# LokomotivRevB.net
KiCad netlist of a schematic drawn in EAGLE
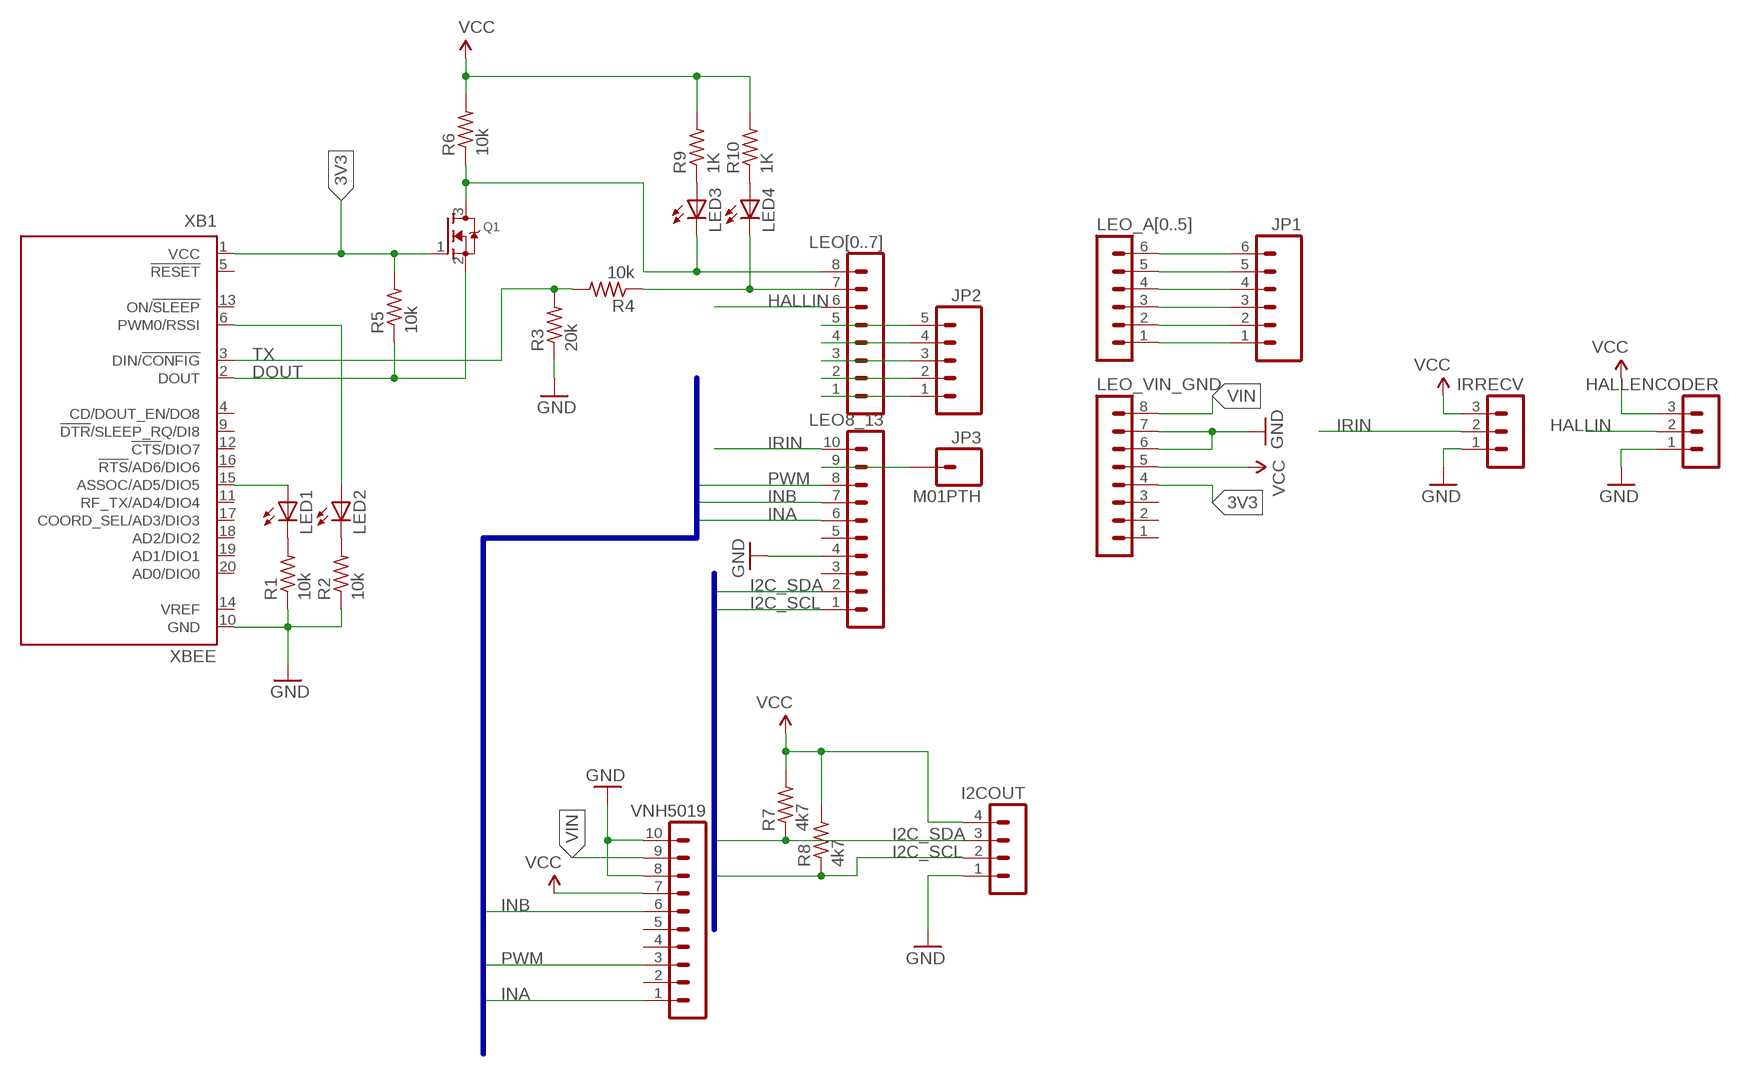
[diagram p0: schematic, sheet 1]

(export (version "E")
  (design (tool "Eeschema 10.0.6"))
  (components
    (comp (ref "HALLENCODER")
      (value "MA03-1")
      (footprint "eagle-import:MA03-1")
      (libsource (lib "eagle-import") (part "MA03-1"))
    )
    (comp (ref "I2COUT")
      (value "MA04-1")
      (footprint "eagle-import:MA04-1")
      (libsource (lib "eagle-import") (part "MA04-1"))
    )
    (comp (ref "IRRECV")
      (value "MA03-1")
      (footprint "eagle-import:MA03-1")
      (libsource (lib "eagle-import") (part "MA03-1"))
    )
    (comp (ref "JP1")
      (value "M06SIP")
      (footprint "eagle-import:1X06")
      (libsource (lib "eagle-import") (part "M06SIP"))
    )
    (comp (ref "JP2")
      (value "M05PTH")
      (footprint "eagle-import:1X05")
      (libsource (lib "eagle-import") (part "M05PTH"))
    )
    (comp (ref "JP3")
      (value "M01PTH")
      (footprint "eagle-import:1X01")
      (libsource (lib "eagle-import") (part "M01PTH"))
    )
    (comp (ref "LED1")
      (value "LEDCHIP-LED0805")
      (footprint "eagle-import:CHIP-LED0805")
      (libsource (lib "eagle-import") (part "LEDCHIP-LED0805"))
    )
    (comp (ref "LED2")
      (value "LEDCHIP-LED0805")
      (footprint "eagle-import:CHIP-LED0805")
      (libsource (lib "eagle-import") (part "LEDCHIP-LED0805"))
    )
    (comp (ref "LED3")
      (value "LEDCHIP-LED0805")
      (footprint "eagle-import:CHIP-LED0805")
      (libsource (lib "eagle-import") (part "LEDCHIP-LED0805"))
    )
    (comp (ref "LED4")
      (value "LEDCHIP-LED0805")
      (footprint "eagle-import:CHIP-LED0805")
      (libsource (lib "eagle-import") (part "LEDCHIP-LED0805"))
    )
    (comp (ref "LEO8_13")
      (value "MA10-1")
      (footprint "eagle-import:MA10-1")
      (libsource (lib "eagle-import") (part "MA10-1"))
    )
    (comp (ref "LEO[0..7]")
      (value "MA08-1")
      (footprint "eagle-import:MA08-1")
      (libsource (lib "eagle-import") (part "MA08-1"))
    )
    (comp (ref "LEO_A[0..5]")
      (value "MA06-1")
      (footprint "eagle-import:MA06-1")
      (libsource (lib "eagle-import") (part "MA06-1"))
    )
    (comp (ref "LEO_VIN_GND")
      (value "MA08-1")
      (footprint "eagle-import:MA08-1")
      (libsource (lib "eagle-import") (part "MA08-1"))
    )
    (comp (ref "Q1")
      (value "MOSFET-NREFLOW")
      (footprint "eagle-import:SOT23")
      (libsource (lib "eagle-import") (part "MOSFET-NREFLOW"))
    )
    (comp (ref "R1")
      (value "10k")
      (footprint "eagle-import:R0805")
      (libsource (lib "eagle-import") (part "R-US_R0805"))
    )
    (comp (ref "R2")
      (value "10k")
      (footprint "eagle-import:R0805")
      (libsource (lib "eagle-import") (part "R-US_R0805"))
    )
    (comp (ref "R3")
      (value "20k")
      (footprint "eagle-import:R0805")
      (libsource (lib "eagle-import") (part "R-US_R0805"))
    )
    (comp (ref "R4")
      (value "10k")
      (footprint "eagle-import:R0805")
      (libsource (lib "eagle-import") (part "R-US_R0805"))
    )
    (comp (ref "R5")
      (value "10k")
      (footprint "eagle-import:R0805")
      (libsource (lib "eagle-import") (part "R-US_R0805"))
    )
    (comp (ref "R6")
      (value "10k")
      (footprint "eagle-import:R0805")
      (libsource (lib "eagle-import") (part "R-US_R0805"))
    )
    (comp (ref "R7")
      (value "4k7")
      (footprint "eagle-import:R0805")
      (libsource (lib "eagle-import") (part "R-US_R0805"))
    )
    (comp (ref "R8")
      (value "4k7")
      (footprint "eagle-import:R0805")
      (libsource (lib "eagle-import") (part "R-US_R0805"))
    )
    (comp (ref "R9")
      (value "1K")
      (footprint "eagle-import:R0805")
      (libsource (lib "eagle-import") (part "R-US_R0805"))
    )
    (comp (ref "R10")
      (value "1K")
      (footprint "eagle-import:R0805")
      (libsource (lib "eagle-import") (part "R-US_R0805"))
    )
    (comp (ref "VNH5019")
      (value "MA10-1")
      (footprint "eagle-import:MA10-1")
      (libsource (lib "eagle-import") (part "MA10-1"))
    )
    (comp (ref "XB1")
      (value "XBEE")
      (footprint "eagle-import:XBEE")
      (fields (field (name "MPN") "XBP24-Z7UIT-004"))
      (libsource (lib "eagle-import") (part "XBEE"))
    )
  )
  (nets
    (net (code "1") (name "/DOUT") (class "Default")
      (node (ref "Q1") (pin "2") (pinfunction "S_2") (pintype "bidirectional"))
      (node (ref "R5") (pin "1") (pinfunction "1_1") (pintype "passive"))
      (node (ref "XB1") (pin "2") (pinfunction "DOUT_2") (pintype "output"))
    )
    (net (code "2") (name "/HALLIN") (class "Default")
      (node (ref "HALLENCODER") (pin "2") (pinfunction "2_2") (pintype "passive"))
      (node (ref "LEO[0..7]") (pin "6") (pinfunction "6_6") (pintype "passive"))
    )
    (net (code "3") (name "/I2C_SCL") (class "Default")
      (node (ref "I2COUT") (pin "2") (pinfunction "2_2") (pintype "passive"))
      (node (ref "LEO8_13") (pin "1") (pinfunction "1_1") (pintype "passive"))
      (node (ref "R8") (pin "1") (pinfunction "1_1") (pintype "passive"))
    )
    (net (code "4") (name "/I2C_SDA") (class "Default")
      (node (ref "I2COUT") (pin "3") (pinfunction "3_3") (pintype "passive"))
      (node (ref "LEO8_13") (pin "2") (pinfunction "2_2") (pintype "passive"))
      (node (ref "R7") (pin "1") (pinfunction "1_1") (pintype "passive"))
    )
    (net (code "5") (name "/INA") (class "Default")
      (node (ref "LEO8_13") (pin "6") (pinfunction "6_6") (pintype "passive"))
      (node (ref "VNH5019") (pin "1") (pinfunction "1_1") (pintype "passive"))
    )
    (net (code "6") (name "/INB") (class "Default")
      (node (ref "LEO8_13") (pin "7") (pinfunction "7_7") (pintype "passive"))
      (node (ref "VNH5019") (pin "6") (pinfunction "6_6") (pintype "passive"))
    )
    (net (code "7") (name "/IRIN") (class "Default")
      (node (ref "IRRECV") (pin "2") (pinfunction "2_2") (pintype "passive"))
      (node (ref "LEO8_13") (pin "10") (pinfunction "10_10") (pintype "passive"))
    )
    (net (code "8") (name "/PWM") (class "Default")
      (node (ref "LEO8_13") (pin "8") (pinfunction "8_8") (pintype "passive"))
      (node (ref "VNH5019") (pin "3") (pinfunction "3_3") (pintype "passive"))
    )
    (net (code "9") (name "/TX") (class "Default")
      (node (ref "R3") (pin "2") (pinfunction "2_2") (pintype "passive"))
      (node (ref "R4") (pin "2") (pinfunction "2_2") (pintype "passive"))
      (node (ref "XB1") (pin "3") (pinfunction "DIN/~{CONFIG}_3") (pintype "input"))
    )
    (net (code "10") (name "3V3") (class "Default")
      (node (ref "LEO_VIN_GND") (pin "4") (pinfunction "4_4") (pintype "passive"))
      (node (ref "Q1") (pin "1") (pinfunction "G_1") (pintype "bidirectional"))
      (node (ref "R5") (pin "2") (pinfunction "2_2") (pintype "passive"))
      (node (ref "XB1") (pin "1") (pinfunction "VCC_1") (pintype "power_in"))
    )
    (net (code "11") (name "GND") (class "Default")
      (node (ref "HALLENCODER") (pin "1") (pinfunction "1_1") (pintype "passive"))
      (node (ref "I2COUT") (pin "1") (pinfunction "1_1") (pintype "passive"))
      (node (ref "IRRECV") (pin "1") (pinfunction "1_1") (pintype "passive"))
      (node (ref "LEO8_13") (pin "4") (pinfunction "4_4") (pintype "passive"))
      (node (ref "LEO_VIN_GND") (pin "6") (pinfunction "6_6") (pintype "passive"))
      (node (ref "LEO_VIN_GND") (pin "7") (pinfunction "7_7") (pintype "passive"))
      (node (ref "R1") (pin "1") (pinfunction "1_1") (pintype "passive"))
      (node (ref "R2") (pin "1") (pinfunction "1_1") (pintype "passive"))
      (node (ref "R3") (pin "1") (pinfunction "1_1") (pintype "passive"))
      (node (ref "VNH5019") (pin "10") (pinfunction "10_10") (pintype "passive"))
      (node (ref "VNH5019") (pin "8") (pinfunction "8_8") (pintype "passive"))
      (node (ref "XB1") (pin "10") (pinfunction "GND_10") (pintype "power_in"))
    )
    (net (code "12") (name "Net-(JP1-Pad1)") (class "Default")
      (node (ref "JP1") (pin "1") (pinfunction "1_1") (pintype "passive"))
      (node (ref "LEO_A[0..5]") (pin "1") (pinfunction "1_1") (pintype "passive"))
    )
    (net (code "13") (name "Net-(JP1-Pad2)") (class "Default")
      (node (ref "JP1") (pin "2") (pinfunction "2_2") (pintype "passive"))
      (node (ref "LEO_A[0..5]") (pin "2") (pinfunction "2_2") (pintype "passive"))
    )
    (net (code "14") (name "Net-(JP1-Pad3)") (class "Default")
      (node (ref "JP1") (pin "3") (pinfunction "3_3") (pintype "passive"))
      (node (ref "LEO_A[0..5]") (pin "3") (pinfunction "3_3") (pintype "passive"))
    )
    (net (code "15") (name "Net-(JP1-Pad4)") (class "Default")
      (node (ref "JP1") (pin "4") (pinfunction "4_4") (pintype "passive"))
      (node (ref "LEO_A[0..5]") (pin "4") (pinfunction "4_4") (pintype "passive"))
    )
    (net (code "16") (name "Net-(JP1-Pad5)") (class "Default")
      (node (ref "JP1") (pin "5") (pinfunction "5_5") (pintype "passive"))
      (node (ref "LEO_A[0..5]") (pin "5") (pinfunction "5_5") (pintype "passive"))
    )
    (net (code "17") (name "Net-(JP1-Pad6)") (class "Default")
      (node (ref "JP1") (pin "6") (pinfunction "6_6") (pintype "passive"))
      (node (ref "LEO_A[0..5]") (pin "6") (pinfunction "6_6") (pintype "passive"))
    )
    (net (code "18") (name "Net-(JP2-Pad1)") (class "Default")
      (node (ref "JP2") (pin "1") (pinfunction "1_1") (pintype "passive"))
      (node (ref "LEO[0..7]") (pin "1") (pinfunction "1_1") (pintype "passive"))
    )
    (net (code "19") (name "Net-(JP2-Pad2)") (class "Default")
      (node (ref "JP2") (pin "2") (pinfunction "2_2") (pintype "passive"))
      (node (ref "LEO[0..7]") (pin "2") (pinfunction "2_2") (pintype "passive"))
    )
    (net (code "20") (name "Net-(JP2-Pad3)") (class "Default")
      (node (ref "JP2") (pin "3") (pinfunction "3_3") (pintype "passive"))
      (node (ref "LEO[0..7]") (pin "3") (pinfunction "3_3") (pintype "passive"))
    )
    (net (code "21") (name "Net-(JP2-Pad4)") (class "Default")
      (node (ref "JP2") (pin "4") (pinfunction "4_4") (pintype "passive"))
      (node (ref "LEO[0..7]") (pin "4") (pinfunction "4_4") (pintype "passive"))
    )
    (net (code "22") (name "Net-(JP2-Pad5)") (class "Default")
      (node (ref "JP2") (pin "5") (pinfunction "5_5") (pintype "passive"))
      (node (ref "LEO[0..7]") (pin "5") (pinfunction "5_5") (pintype "passive"))
    )
    (net (code "23") (name "Net-(JP3-Pad1)") (class "Default")
      (node (ref "JP3") (pin "1") (pinfunction "1_1") (pintype "passive"))
      (node (ref "LEO8_13") (pin "9") (pinfunction "9_9") (pintype "passive"))
    )
    (net (code "24") (name "Net-(LED1-PadC)") (class "Default")
      (node (ref "LED1") (pin "C") (pinfunction "C_C") (pintype "passive"))
      (node (ref "R1") (pin "2") (pinfunction "2_2") (pintype "passive"))
    )
    (net (code "25") (name "Net-(LED2-PadC)") (class "Default")
      (node (ref "LED2") (pin "C") (pinfunction "C_C") (pintype "passive"))
      (node (ref "R2") (pin "2") (pinfunction "2_2") (pintype "passive"))
    )
    (net (code "26") (name "Net-(LED3-PadA)") (class "Default")
      (node (ref "LED3") (pin "A") (pinfunction "A_A") (pintype "passive"))
      (node (ref "R9") (pin "1") (pinfunction "1_1") (pintype "passive"))
    )
    (net (code "27") (name "Net-(LED4-PadA)") (class "Default")
      (node (ref "LED4") (pin "A") (pinfunction "A_A") (pintype "passive"))
      (node (ref "R10") (pin "1") (pinfunction "1_1") (pintype "passive"))
    )
    (net (code "28") (name "Net-(LED4-PadC)") (class "Default")
      (node (ref "LED4") (pin "C") (pinfunction "C_C") (pintype "passive"))
      (node (ref "LEO[0..7]") (pin "7") (pinfunction "7_7") (pintype "passive"))
      (node (ref "R4") (pin "1") (pinfunction "1_1") (pintype "passive"))
    )
    (net (code "29") (name "Net-(Q1-D)") (class "Default")
      (node (ref "LED3") (pin "C") (pinfunction "C_C") (pintype "passive"))
      (node (ref "LEO[0..7]") (pin "8") (pinfunction "8_8") (pintype "passive"))
      (node (ref "Q1") (pin "3") (pinfunction "D_3") (pintype "bidirectional"))
      (node (ref "R6") (pin "1") (pinfunction "1_1") (pintype "passive"))
    )
    (net (code "30") (name "Net-(XB1-ASSOC{slash}AD5{slash}DIO5)") (class "Default")
      (node (ref "LED1") (pin "A") (pinfunction "A_A") (pintype "passive"))
      (node (ref "XB1") (pin "15") (pinfunction "ASSOC/AD5/DIO5_15") (pintype "bidirectional"))
    )
    (net (code "31") (name "Net-(XB1-PWM0{slash}RSSI)") (class "Default")
      (node (ref "LED2") (pin "A") (pinfunction "A_A") (pintype "passive"))
      (node (ref "XB1") (pin "6") (pinfunction "PWM0/RSSI_6") (pintype "output"))
    )
    (net (code "32") (name "VCC") (class "Default")
      (node (ref "HALLENCODER") (pin "3") (pinfunction "3_3") (pintype "passive"))
      (node (ref "I2COUT") (pin "4") (pinfunction "4_4") (pintype "passive"))
      (node (ref "IRRECV") (pin "3") (pinfunction "3_3") (pintype "passive"))
      (node (ref "LEO_VIN_GND") (pin "5") (pinfunction "5_5") (pintype "passive"))
      (node (ref "R10") (pin "2") (pinfunction "2_2") (pintype "passive"))
      (node (ref "R6") (pin "2") (pinfunction "2_2") (pintype "passive"))
      (node (ref "R7") (pin "2") (pinfunction "2_2") (pintype "passive"))
      (node (ref "R8") (pin "2") (pinfunction "2_2") (pintype "passive"))
      (node (ref "R9") (pin "2") (pinfunction "2_2") (pintype "passive"))
      (node (ref "VNH5019") (pin "7") (pinfunction "7_7") (pintype "passive"))
    )
    (net (code "33") (name "VIN") (class "Default")
      (node (ref "LEO_VIN_GND") (pin "8") (pinfunction "8_8") (pintype "passive"))
      (node (ref "VNH5019") (pin "9") (pinfunction "9_9") (pintype "passive"))
    )
    (net (code "34") (name "unconnected-(LEO8_13-Pad3)") (class "Default")
      (node (ref "LEO8_13") (pin "3") (pinfunction "3_3") (pintype "passive"))
    )
    (net (code "35") (name "unconnected-(LEO8_13-Pad5)") (class "Default")
      (node (ref "LEO8_13") (pin "5") (pinfunction "5_5") (pintype "passive"))
    )
    (net (code "36") (name "unconnected-(LEO_VIN_GND-Pad1)") (class "Default")
      (node (ref "LEO_VIN_GND") (pin "1") (pinfunction "1_1") (pintype "passive"))
    )
    (net (code "37") (name "unconnected-(LEO_VIN_GND-Pad2)") (class "Default")
      (node (ref "LEO_VIN_GND") (pin "2") (pinfunction "2_2") (pintype "passive"))
    )
    (net (code "38") (name "unconnected-(LEO_VIN_GND-Pad3)") (class "Default")
      (node (ref "LEO_VIN_GND") (pin "3") (pinfunction "3_3") (pintype "passive"))
    )
    (net (code "39") (name "unconnected-(VNH5019-Pad2)") (class "Default")
      (node (ref "VNH5019") (pin "2") (pinfunction "2_2") (pintype "passive"))
    )
    (net (code "40") (name "unconnected-(VNH5019-Pad4)") (class "Default")
      (node (ref "VNH5019") (pin "4") (pinfunction "4_4") (pintype "passive"))
    )
    (net (code "41") (name "unconnected-(VNH5019-Pad5)") (class "Default")
      (node (ref "VNH5019") (pin "5") (pinfunction "5_5") (pintype "passive"))
    )
    (net (code "42") (name "unconnected-(XB1-AD0{slash}DIO0-Pad20)") (class "Default")
      (node (ref "XB1") (pin "20") (pinfunction "AD0/DIO0_20") (pintype "bidirectional"))
    )
    (net (code "43") (name "unconnected-(XB1-AD1{slash}DIO1-Pad19)") (class "Default")
      (node (ref "XB1") (pin "19") (pinfunction "AD1/DIO1_19") (pintype "bidirectional"))
    )
    (net (code "44") (name "unconnected-(XB1-AD2{slash}DIO2-Pad18)") (class "Default")
      (node (ref "XB1") (pin "18") (pinfunction "AD2/DIO2_18") (pintype "bidirectional"))
    )
    (net (code "45") (name "unconnected-(XB1-CD{slash}DOUT_EN{slash}DO8-Pad4)") (class "Default")
      (node (ref "XB1") (pin "4") (pinfunction "CD/DOUT_EN/DO8_4") (pintype "output"))
    )
    (net (code "46") (name "unconnected-(XB1-COORD_SEL{slash}AD3{slash}DIO3-Pad17)") (class "Default")
      (node (ref "XB1") (pin "17") (pinfunction "COORD_SEL/AD3/DIO3_17") (pintype "bidirectional"))
    )
    (net (code "47") (name "unconnected-(XB1-ON{slash}~{SLEEP}-Pad13)") (class "Default")
      (node (ref "XB1") (pin "13") (pinfunction "ON/~{SLEEP}_13") (pintype "output"))
    )
    (net (code "48") (name "unconnected-(XB1-RF_TX{slash}AD4{slash}DIO4-Pad11)") (class "Default")
      (node (ref "XB1") (pin "11") (pinfunction "RF_TX/AD4/DIO4_11") (pintype "bidirectional"))
    )
    (net (code "49") (name "unconnected-(XB1-VREF-Pad14)") (class "Default")
      (node (ref "XB1") (pin "14") (pinfunction "VREF_14") (pintype "input"))
    )
    (net (code "50") (name "unconnected-(XB1-~{CTS}{slash}DIO7-Pad12)") (class "Default")
      (node (ref "XB1") (pin "12") (pinfunction "~{CTS}/DIO7_12") (pintype "bidirectional"))
    )
    (net (code "51") (name "unconnected-(XB1-~{DTR}{slash}SLEEP_RQ{slash}DI8-Pad9)") (class "Default")
      (node (ref "XB1") (pin "9") (pinfunction "~{DTR}/SLEEP_RQ/DI8_9") (pintype "bidirectional"))
    )
    (net (code "52") (name "unconnected-(XB1-~{RESET}-Pad5)") (class "Default")
      (node (ref "XB1") (pin "5") (pinfunction "~{RESET}_5") (pintype "input"))
    )
    (net (code "53") (name "unconnected-(XB1-~{RTS}{slash}AD6{slash}DIO6-Pad16)") (class "Default")
      (node (ref "XB1") (pin "16") (pinfunction "~{RTS}/AD6/DIO6_16") (pintype "bidirectional"))
    )
  )
)
